# sch_ma_logique.net
KiCad netlist of a schematic drawn in EAGLE
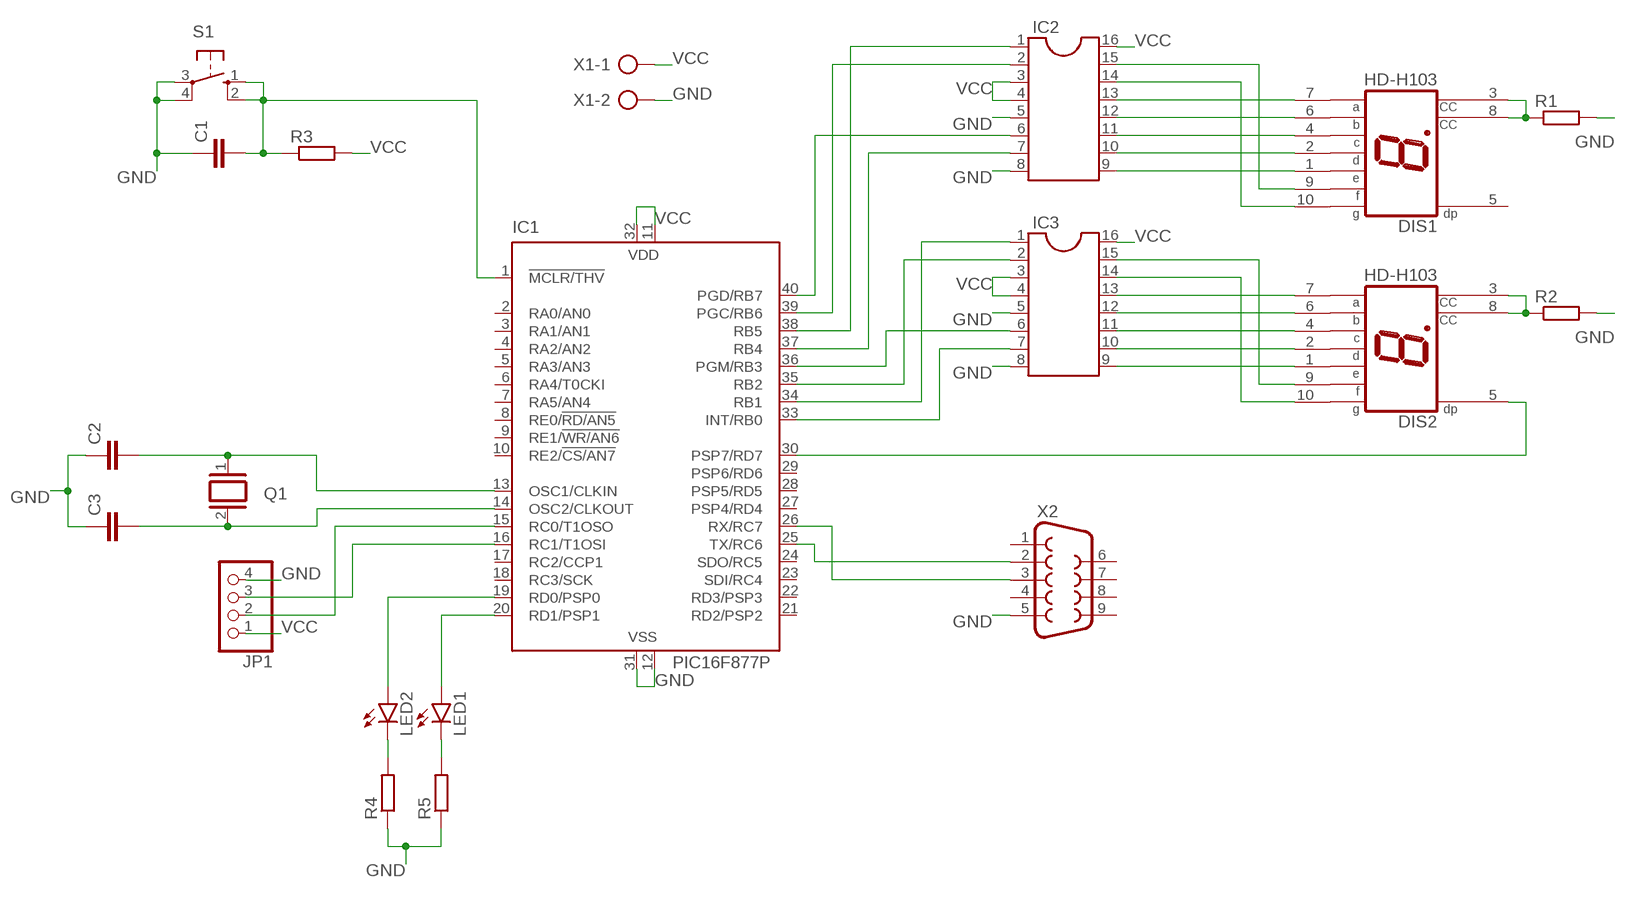
[diagram p0: schematic, sheet 1]

(export (version "E")
  (design (tool "Eeschema 10.0.6"))
  (components
    (comp (ref "C1")
      (value "C-EU025-025X050")
      (footprint "eagle-import:C025-025X050")
      (libsource (lib "eagle-import") (part "C-EU025-025X050"))
    )
    (comp (ref "C2")
      (value "C-EU025-025X050")
      (footprint "eagle-import:C025-025X050")
      (libsource (lib "eagle-import") (part "C-EU025-025X050"))
    )
    (comp (ref "C3")
      (value "C-EU025-025X050")
      (footprint "eagle-import:C025-025X050")
      (libsource (lib "eagle-import") (part "C-EU025-025X050"))
    )
    (comp (ref "DIS1")
      (value "HD-H103")
      (footprint "eagle-import:HDSP-M")
      (libsource (lib "eagle-import") (part "HD-H103"))
    )
    (comp (ref "DIS2")
      (value "HD-H103")
      (footprint "eagle-import:HDSP-M")
      (libsource (lib "eagle-import") (part "HD-H103"))
    )
    (comp (ref "IC1")
      (value "PIC16F877P")
      (footprint "eagle-import:DIL40")
      (fields (field (name "MF") "MICROCHIP") (field (name "MPN") "PIC16F877-04/P"))
      (libsource (lib "eagle-import") (part "PIC16F87P7"))
    )
    (comp (ref "IC2")
      (value "DIL16")
      (footprint "eagle-import:DIL16")
      (libsource (lib "eagle-import") (part "DIL16"))
    )
    (comp (ref "IC3")
      (value "DIL16")
      (footprint "eagle-import:DIL16")
      (libsource (lib "eagle-import") (part "DIL16"))
    )
    (comp (ref "JP1")
      (value "PINHD-1X4")
      (footprint "eagle-import:1X04")
      (libsource (lib "eagle-import") (part "PINHD-1X4"))
    )
    (comp (ref "LED1")
      (value "LED5MM")
      (footprint "eagle-import:LED5MM")
      (libsource (lib "eagle-import") (part "LED5MM"))
    )
    (comp (ref "LED2")
      (value "LED5MM")
      (footprint "eagle-import:LED5MM")
      (libsource (lib "eagle-import") (part "LED5MM"))
    )
    (comp (ref "Q1")
      (value "XTAL/S")
      (footprint "eagle-import:QS")
      (libsource (lib "eagle-import") (part "XTAL/S"))
    )
    (comp (ref "R1")
      (value "R-EU_0207/10")
      (footprint "eagle-import:0207_10")
      (libsource (lib "eagle-import") (part "R-EU_0207/10"))
    )
    (comp (ref "R2")
      (value "R-EU_0207/10")
      (footprint "eagle-import:0207_10")
      (libsource (lib "eagle-import") (part "R-EU_0207/10"))
    )
    (comp (ref "R3")
      (value "R-EU_0207/10")
      (footprint "eagle-import:0207_10")
      (libsource (lib "eagle-import") (part "R-EU_0207/10"))
    )
    (comp (ref "R4")
      (value "R-EU_0207/10")
      (footprint "eagle-import:0207_10")
      (libsource (lib "eagle-import") (part "R-EU_0207/10"))
    )
    (comp (ref "R5")
      (value "R-EU_0207/10")
      (footprint "eagle-import:0207_10")
      (libsource (lib "eagle-import") (part "R-EU_0207/10"))
    )
    (comp (ref "S1")
      (value "10-XX")
      (footprint "eagle-import:B3F-10XX")
      (fields (field (name "MPN") "B3F-1000"))
      (libsource (lib "eagle-import") (part "10-XX"))
    )
    (comp (ref "X1")
      (value "AK300/2")
      (footprint "eagle-import:AK300_2")
      (libsource (lib "eagle-import") (part "AK300/2"))
    )
    (comp (ref "X2")
      (value "F09H")
      (footprint "eagle-import:F09H")
      (libsource (lib "eagle-import") (part "F09H"))
    )
  )
  (nets
    (net (code "1") (name "/GND") (class "Default")
      (node (ref "C1") (pin "1") (pinfunction "1_1") (pintype "passive"))
      (node (ref "C2") (pin "1") (pinfunction "1_1") (pintype "passive"))
      (node (ref "C3") (pin "1") (pinfunction "1_1") (pintype "passive"))
      (node (ref "IC1") (pin "12") (pinfunction "VSS_12") (pintype "power_in"))
      (node (ref "IC1") (pin "31") (pinfunction "VSS_31") (pintype "power_in"))
      (node (ref "IC2") (pin "5") (pinfunction "5_5") (pintype "passive"))
      (node (ref "IC2") (pin "8") (pinfunction "8_8") (pintype "passive"))
      (node (ref "IC3") (pin "5") (pinfunction "5_5") (pintype "passive"))
      (node (ref "IC3") (pin "8") (pinfunction "8_8") (pintype "passive"))
      (node (ref "JP1") (pin "4") (pinfunction "4_4") (pintype "passive"))
      (node (ref "R1") (pin "2") (pinfunction "2_2") (pintype "passive"))
      (node (ref "R2") (pin "2") (pinfunction "2_2") (pintype "passive"))
      (node (ref "R4") (pin "1") (pinfunction "1_1") (pintype "passive"))
      (node (ref "R5") (pin "1") (pinfunction "1_1") (pintype "passive"))
      (node (ref "S1") (pin "3") (pinfunction "P_3") (pintype "passive"))
      (node (ref "S1") (pin "4") (pinfunction "P1_4") (pintype "passive"))
      (node (ref "X1") (pin "2") (pinfunction "KL_2") (pintype "passive"))
      (node (ref "X2") (pin "5") (pinfunction "5_5") (pintype "passive"))
    )
    (net (code "2") (name "/VCC") (class "Default")
      (node (ref "IC1") (pin "11") (pinfunction "VDD_11") (pintype "power_in"))
      (node (ref "IC1") (pin "32") (pinfunction "VDD_32") (pintype "power_in"))
      (node (ref "IC2") (pin "16") (pinfunction "16_16") (pintype "passive"))
      (node (ref "IC2") (pin "3") (pinfunction "3_3") (pintype "passive"))
      (node (ref "IC2") (pin "4") (pinfunction "4_4") (pintype "passive"))
      (node (ref "IC3") (pin "16") (pinfunction "16_16") (pintype "passive"))
      (node (ref "IC3") (pin "3") (pinfunction "3_3") (pintype "passive"))
      (node (ref "IC3") (pin "4") (pinfunction "4_4") (pintype "passive"))
      (node (ref "JP1") (pin "1") (pinfunction "1_1") (pintype "passive"))
      (node (ref "R3") (pin "2") (pinfunction "2_2") (pintype "passive"))
      (node (ref "X1") (pin "1") (pinfunction "KL_1") (pintype "passive"))
    )
    (net (code "3") (name "Net-(DIS1-A)") (class "Default")
      (node (ref "DIS1") (pin "7") (pinfunction "A_7") (pintype "passive"))
      (node (ref "IC2") (pin "13") (pinfunction "13_13") (pintype "passive"))
    )
    (net (code "4") (name "Net-(DIS1-B)") (class "Default")
      (node (ref "DIS1") (pin "6") (pinfunction "B_6") (pintype "passive"))
      (node (ref "IC2") (pin "12") (pinfunction "12_12") (pintype "passive"))
    )
    (net (code "5") (name "Net-(DIS1-C)") (class "Default")
      (node (ref "DIS1") (pin "4") (pinfunction "C_4") (pintype "passive"))
      (node (ref "IC2") (pin "11") (pinfunction "11_11") (pintype "passive"))
    )
    (net (code "6") (name "Net-(DIS1-CC-Pad3)") (class "Default")
      (node (ref "DIS1") (pin "3") (pinfunction "CC_3") (pintype "passive"))
      (node (ref "DIS1") (pin "8") (pinfunction "CC_8") (pintype "passive"))
      (node (ref "R1") (pin "1") (pinfunction "1_1") (pintype "passive"))
    )
    (net (code "7") (name "Net-(DIS1-D)") (class "Default")
      (node (ref "DIS1") (pin "2") (pinfunction "D_2") (pintype "passive"))
      (node (ref "IC2") (pin "10") (pinfunction "10_10") (pintype "passive"))
    )
    (net (code "8") (name "Net-(DIS1-E)") (class "Default")
      (node (ref "DIS1") (pin "1") (pinfunction "E_1") (pintype "passive"))
      (node (ref "IC2") (pin "9") (pinfunction "9_9") (pintype "passive"))
    )
    (net (code "9") (name "Net-(DIS1-F)") (class "Default")
      (node (ref "DIS1") (pin "9") (pinfunction "F_9") (pintype "passive"))
      (node (ref "IC2") (pin "15") (pinfunction "15_15") (pintype "passive"))
    )
    (net (code "10") (name "Net-(DIS1-G)") (class "Default")
      (node (ref "DIS1") (pin "10") (pinfunction "G_10") (pintype "passive"))
      (node (ref "IC2") (pin "14") (pinfunction "14_14") (pintype "passive"))
    )
    (net (code "11") (name "Net-(DIS2-A)") (class "Default")
      (node (ref "DIS2") (pin "7") (pinfunction "A_7") (pintype "passive"))
      (node (ref "IC3") (pin "13") (pinfunction "13_13") (pintype "passive"))
    )
    (net (code "12") (name "Net-(DIS2-B)") (class "Default")
      (node (ref "DIS2") (pin "6") (pinfunction "B_6") (pintype "passive"))
      (node (ref "IC3") (pin "12") (pinfunction "12_12") (pintype "passive"))
    )
    (net (code "13") (name "Net-(DIS2-C)") (class "Default")
      (node (ref "DIS2") (pin "4") (pinfunction "C_4") (pintype "passive"))
      (node (ref "IC3") (pin "11") (pinfunction "11_11") (pintype "passive"))
    )
    (net (code "14") (name "Net-(DIS2-CC-Pad3)") (class "Default")
      (node (ref "DIS2") (pin "3") (pinfunction "CC_3") (pintype "passive"))
      (node (ref "DIS2") (pin "8") (pinfunction "CC_8") (pintype "passive"))
      (node (ref "R2") (pin "1") (pinfunction "1_1") (pintype "passive"))
    )
    (net (code "15") (name "Net-(DIS2-D)") (class "Default")
      (node (ref "DIS2") (pin "2") (pinfunction "D_2") (pintype "passive"))
      (node (ref "IC3") (pin "10") (pinfunction "10_10") (pintype "passive"))
    )
    (net (code "16") (name "Net-(DIS2-DP)") (class "Default")
      (node (ref "DIS2") (pin "5") (pinfunction "DP_5") (pintype "passive"))
      (node (ref "IC1") (pin "30") (pinfunction "PSP7/RD7_30") (pintype "bidirectional"))
    )
    (net (code "17") (name "Net-(DIS2-E)") (class "Default")
      (node (ref "DIS2") (pin "1") (pinfunction "E_1") (pintype "passive"))
      (node (ref "IC3") (pin "9") (pinfunction "9_9") (pintype "passive"))
    )
    (net (code "18") (name "Net-(DIS2-F)") (class "Default")
      (node (ref "DIS2") (pin "9") (pinfunction "F_9") (pintype "passive"))
      (node (ref "IC3") (pin "15") (pinfunction "15_15") (pintype "passive"))
    )
    (net (code "19") (name "Net-(DIS2-G)") (class "Default")
      (node (ref "DIS2") (pin "10") (pinfunction "G_10") (pintype "passive"))
      (node (ref "IC3") (pin "14") (pinfunction "14_14") (pintype "passive"))
    )
    (net (code "20") (name "Net-(IC1-INT{slash}RB0)") (class "Default")
      (node (ref "IC1") (pin "33") (pinfunction "INT/RB0_33") (pintype "bidirectional"))
      (node (ref "IC3") (pin "7") (pinfunction "7_7") (pintype "passive"))
    )
    (net (code "21") (name "Net-(IC1-OSC1{slash}CLKIN)") (class "Default")
      (node (ref "C2") (pin "2") (pinfunction "2_2") (pintype "passive"))
      (node (ref "IC1") (pin "13") (pinfunction "OSC1/CLKIN_13") (pintype "input"))
      (node (ref "Q1") (pin "1") (pinfunction "1_1") (pintype "passive"))
    )
    (net (code "22") (name "Net-(IC1-OSC2{slash}CLKOUT)") (class "Default")
      (node (ref "C3") (pin "2") (pinfunction "2_2") (pintype "passive"))
      (node (ref "IC1") (pin "14") (pinfunction "OSC2/CLKOUT_14") (pintype "output"))
      (node (ref "Q1") (pin "2") (pinfunction "2_2") (pintype "passive"))
    )
    (net (code "23") (name "Net-(IC1-PGC{slash}RB6)") (class "Default")
      (node (ref "IC1") (pin "39") (pinfunction "PGC/RB6_39") (pintype "bidirectional"))
      (node (ref "IC2") (pin "2") (pinfunction "2_2") (pintype "passive"))
    )
    (net (code "24") (name "Net-(IC1-PGD{slash}RB7)") (class "Default")
      (node (ref "IC1") (pin "40") (pinfunction "PGD/RB7_40") (pintype "bidirectional"))
      (node (ref "IC2") (pin "6") (pinfunction "6_6") (pintype "passive"))
    )
    (net (code "25") (name "Net-(IC1-PGM{slash}RB3)") (class "Default")
      (node (ref "IC1") (pin "36") (pinfunction "PGM/RB3_36") (pintype "bidirectional"))
      (node (ref "IC3") (pin "6") (pinfunction "6_6") (pintype "passive"))
    )
    (net (code "26") (name "Net-(IC1-RB1)") (class "Default")
      (node (ref "IC1") (pin "34") (pinfunction "RB1_34") (pintype "bidirectional"))
      (node (ref "IC3") (pin "1") (pinfunction "1_1") (pintype "passive"))
    )
    (net (code "27") (name "Net-(IC1-RB2)") (class "Default")
      (node (ref "IC1") (pin "35") (pinfunction "RB2_35") (pintype "bidirectional"))
      (node (ref "IC3") (pin "2") (pinfunction "2_2") (pintype "passive"))
    )
    (net (code "28") (name "Net-(IC1-RB4)") (class "Default")
      (node (ref "IC1") (pin "37") (pinfunction "RB4_37") (pintype "bidirectional"))
      (node (ref "IC2") (pin "7") (pinfunction "7_7") (pintype "passive"))
    )
    (net (code "29") (name "Net-(IC1-RB5)") (class "Default")
      (node (ref "IC1") (pin "38") (pinfunction "RB5_38") (pintype "bidirectional"))
      (node (ref "IC2") (pin "1") (pinfunction "1_1") (pintype "passive"))
    )
    (net (code "30") (name "Net-(IC1-RC0{slash}T1OSO)") (class "Default")
      (node (ref "IC1") (pin "15") (pinfunction "RC0/T1OSO_15") (pintype "bidirectional"))
      (node (ref "JP1") (pin "2") (pinfunction "2_2") (pintype "passive"))
    )
    (net (code "31") (name "Net-(IC1-RC1{slash}T1OSI)") (class "Default")
      (node (ref "IC1") (pin "16") (pinfunction "RC1/T1OSI_16") (pintype "bidirectional"))
      (node (ref "JP1") (pin "3") (pinfunction "3_3") (pintype "passive"))
    )
    (net (code "32") (name "Net-(IC1-RD0{slash}PSP0)") (class "Default")
      (node (ref "IC1") (pin "19") (pinfunction "RD0/PSP0_19") (pintype "bidirectional"))
      (node (ref "LED2") (pin "A") (pinfunction "A_A") (pintype "passive"))
    )
    (net (code "33") (name "Net-(IC1-RD1{slash}PSP1)") (class "Default")
      (node (ref "IC1") (pin "20") (pinfunction "RD1/PSP1_20") (pintype "bidirectional"))
      (node (ref "LED1") (pin "A") (pinfunction "A_A") (pintype "passive"))
    )
    (net (code "34") (name "Net-(IC1-RX{slash}RC7)") (class "Default")
      (node (ref "IC1") (pin "26") (pinfunction "RX/RC7_26") (pintype "bidirectional"))
      (node (ref "X2") (pin "3") (pinfunction "3_3") (pintype "passive"))
    )
    (net (code "35") (name "Net-(IC1-TX{slash}RC6)") (class "Default")
      (node (ref "IC1") (pin "25") (pinfunction "TX/RC6_25") (pintype "bidirectional"))
      (node (ref "X2") (pin "2") (pinfunction "2_2") (pintype "passive"))
    )
    (net (code "36") (name "Net-(IC1-~{MCLR{slash}THV})") (class "Default")
      (node (ref "C1") (pin "2") (pinfunction "2_2") (pintype "passive"))
      (node (ref "IC1") (pin "1") (pinfunction "~{MCLR/THV}_1") (pintype "input"))
      (node (ref "R3") (pin "1") (pinfunction "1_1") (pintype "passive"))
      (node (ref "S1") (pin "1") (pinfunction "S_1") (pintype "passive"))
      (node (ref "S1") (pin "2") (pinfunction "S1_2") (pintype "passive"))
    )
    (net (code "37") (name "Net-(LED1-C)") (class "Default")
      (node (ref "LED1") (pin "K") (pinfunction "C_K") (pintype "passive"))
      (node (ref "R5") (pin "2") (pinfunction "2_2") (pintype "passive"))
    )
    (net (code "38") (name "Net-(LED2-C)") (class "Default")
      (node (ref "LED2") (pin "K") (pinfunction "C_K") (pintype "passive"))
      (node (ref "R4") (pin "2") (pinfunction "2_2") (pintype "passive"))
    )
    (net (code "39") (name "unconnected-(DIS1-DP-Pad5)") (class "Default")
      (node (ref "DIS1") (pin "5") (pinfunction "DP_5") (pintype "passive"))
    )
    (net (code "40") (name "unconnected-(IC1-PSP4{slash}RD4-Pad27)") (class "Default")
      (node (ref "IC1") (pin "27") (pinfunction "PSP4/RD4_27") (pintype "bidirectional"))
    )
    (net (code "41") (name "unconnected-(IC1-PSP5{slash}RD5-Pad28)") (class "Default")
      (node (ref "IC1") (pin "28") (pinfunction "PSP5/RD5_28") (pintype "bidirectional"))
    )
    (net (code "42") (name "unconnected-(IC1-PSP6{slash}RD6-Pad29)") (class "Default")
      (node (ref "IC1") (pin "29") (pinfunction "PSP6/RD6_29") (pintype "bidirectional"))
    )
    (net (code "43") (name "unconnected-(IC1-RA0{slash}AN0-Pad2)") (class "Default")
      (node (ref "IC1") (pin "2") (pinfunction "RA0/AN0_2") (pintype "bidirectional"))
    )
    (net (code "44") (name "unconnected-(IC1-RA1{slash}AN1-Pad3)") (class "Default")
      (node (ref "IC1") (pin "3") (pinfunction "RA1/AN1_3") (pintype "bidirectional"))
    )
    (net (code "45") (name "unconnected-(IC1-RA2{slash}AN2-Pad4)") (class "Default")
      (node (ref "IC1") (pin "4") (pinfunction "RA2/AN2_4") (pintype "bidirectional"))
    )
    (net (code "46") (name "unconnected-(IC1-RA3{slash}AN3-Pad5)") (class "Default")
      (node (ref "IC1") (pin "5") (pinfunction "RA3/AN3_5") (pintype "bidirectional"))
    )
    (net (code "47") (name "unconnected-(IC1-RA4{slash}T0CKI-Pad6)") (class "Default")
      (node (ref "IC1") (pin "6") (pinfunction "RA4/T0CKI_6") (pintype "bidirectional"))
    )
    (net (code "48") (name "unconnected-(IC1-RA5{slash}AN4-Pad7)") (class "Default")
      (node (ref "IC1") (pin "7") (pinfunction "RA5/AN4_7") (pintype "bidirectional"))
    )
    (net (code "49") (name "unconnected-(IC1-RC2{slash}CCP1-Pad17)") (class "Default")
      (node (ref "IC1") (pin "17") (pinfunction "RC2/CCP1_17") (pintype "bidirectional"))
    )
    (net (code "50") (name "unconnected-(IC1-RC3{slash}SCK-Pad18)") (class "Default")
      (node (ref "IC1") (pin "18") (pinfunction "RC3/SCK_18") (pintype "bidirectional"))
    )
    (net (code "51") (name "unconnected-(IC1-RD2{slash}PSP2-Pad21)") (class "Default")
      (node (ref "IC1") (pin "21") (pinfunction "RD2/PSP2_21") (pintype "bidirectional"))
    )
    (net (code "52") (name "unconnected-(IC1-RD3{slash}PSP3-Pad22)") (class "Default")
      (node (ref "IC1") (pin "22") (pinfunction "RD3/PSP3_22") (pintype "bidirectional"))
    )
    (net (code "53") (name "unconnected-(IC1-RE0{slash}~{RD{slash}AN5}-Pad8)") (class "Default")
      (node (ref "IC1") (pin "8") (pinfunction "RE0/~{RD/AN5}_8") (pintype "bidirectional"))
    )
    (net (code "54") (name "unconnected-(IC1-RE1{slash}~{WR{slash}AN6}-Pad9)") (class "Default")
      (node (ref "IC1") (pin "9") (pinfunction "RE1/~{WR/AN6}_9") (pintype "bidirectional"))
    )
    (net (code "55") (name "unconnected-(IC1-RE2{slash}~{CS{slash}AN7}-Pad10)") (class "Default")
      (node (ref "IC1") (pin "10") (pinfunction "RE2/~{CS/AN7}_10") (pintype "bidirectional"))
    )
    (net (code "56") (name "unconnected-(IC1-SDI{slash}RC4-Pad23)") (class "Default")
      (node (ref "IC1") (pin "23") (pinfunction "SDI/RC4_23") (pintype "bidirectional"))
    )
    (net (code "57") (name "unconnected-(IC1-SDO{slash}RC5-Pad24)") (class "Default")
      (node (ref "IC1") (pin "24") (pinfunction "SDO/RC5_24") (pintype "bidirectional"))
    )
    (net (code "58") (name "unconnected-(X2-Pad1)") (class "Default")
      (node (ref "X2") (pin "1") (pinfunction "1_1") (pintype "passive"))
    )
    (net (code "59") (name "unconnected-(X2-Pad4)") (class "Default")
      (node (ref "X2") (pin "4") (pinfunction "4_4") (pintype "passive"))
    )
    (net (code "60") (name "unconnected-(X2-Pad6)") (class "Default")
      (node (ref "X2") (pin "6") (pinfunction "6_6") (pintype "passive"))
    )
    (net (code "61") (name "unconnected-(X2-Pad7)") (class "Default")
      (node (ref "X2") (pin "7") (pinfunction "7_7") (pintype "passive"))
    )
    (net (code "62") (name "unconnected-(X2-Pad8)") (class "Default")
      (node (ref "X2") (pin "8") (pinfunction "8_8") (pintype "passive"))
    )
    (net (code "63") (name "unconnected-(X2-Pad9)") (class "Default")
      (node (ref "X2") (pin "9") (pinfunction "9_9") (pintype "passive"))
    )
  )
)
